# 6_RgbLed.net
KiCad netlist of a schematic drawn in Altium Designer
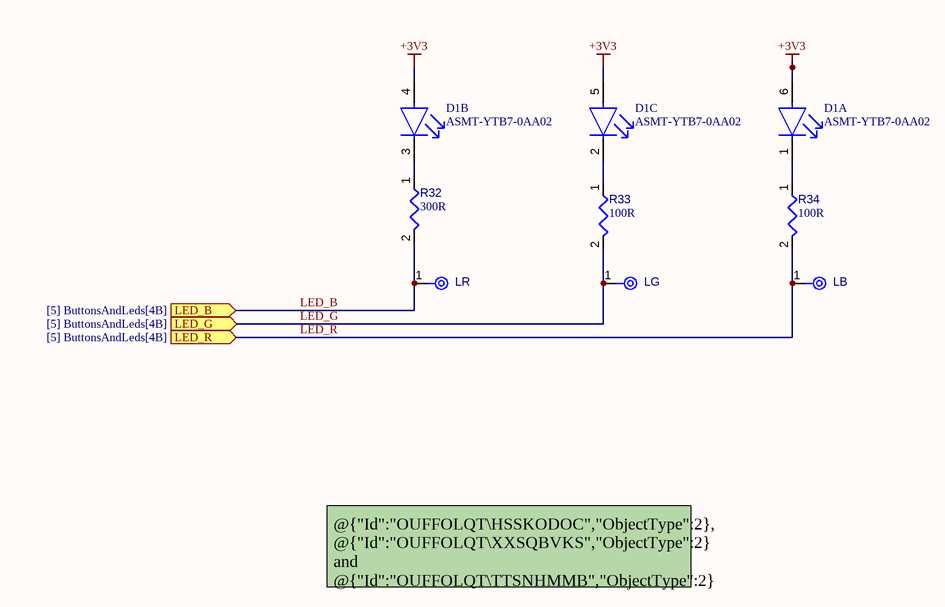
[diagram p0: [6] RgbLed.SchDoc]

(export (version "E")
  (design (tool "Eeschema 10.0.6"))
  (components
    (comp (ref "D1")
      (value "ASMT-YTB7-0AA02")
      (footprint "FP-PLCC-6-MFG")
      (description "LED Tri-Color Blue/Green/Red 469nm/529nm/623nm Chip LED 6-Pin PLCC T/R")
      (libsource (lib "UFCG - Universidade Federal de Campina Grande") (part "0f3d36aaa98356051a15b42400af8f3"))
    )
    (comp (ref "LB")
      (value "TPAD6R")
      (footprint "TP06R")
      (description "0.6mm round")
      (libsource (lib "UFCG - Universidade Federal de Campina Grande") (part "CMP-001-0001-4"))
    )
    (comp (ref "LG")
      (value "TPAD6R")
      (footprint "TP06R")
      (description "0.6mm round")
      (libsource (lib "UFCG - Universidade Federal de Campina Grande") (part "CMP-001-0001-4"))
    )
    (comp (ref "LR")
      (value "TPAD6R")
      (footprint "TP06R")
      (description "0.6mm round")
      (libsource (lib "UFCG - Universidade Federal de Campina Grande") (part "CMP-001-0001-4"))
    )
    (comp (ref "R32")
      (value "300R")
      (footprint "RESC0603(1608)_L")
      (description "Res Thick Film 0603 300 Ohm 5% 1/10W ±200ppm/°C Molded SMD Punched Carrier T/R")
      (fields (field (name "TOLERANCE") "5%") (field (name "Comment") "ERJ-3GEYJ301V"))
      (libsource (lib "UFCG - Universidade Federal de Campina Grande") (part "RES-2"))
    )
    (comp (ref "R33")
      (value "100R")
      (footprint "RESC0603(1608)_L")
      (description "SMD Chip Resistor, 100 Ohm, ï¿½ 1%, 100 mW, 0603 [1608 Metric], Thick Film, Precision")
      (fields (field (name "TOLERANCE") "1%") (field (name "Comment") "ERJ-3EKF1000V"))
      (libsource (lib "UFCG - Universidade Federal de Campina Grande") (part "RES-2"))
    )
    (comp (ref "R34")
      (value "100R")
      (footprint "RESC0603(1608)_L")
      (description "SMD Chip Resistor, 100 Ohm, ï¿½ 1%, 100 mW, 0603 [1608 Metric], Thick Film, Precision")
      (fields (field (name "TOLERANCE") "1%") (field (name "Comment") "ERJ-3EKF1000V"))
      (libsource (lib "UFCG - Universidade Federal de Campina Grande") (part "RES-2"))
    )
  )
  (nets
    (net (code "1") (name "+3V3") (class "Default")
      (node (ref "D1") (pin "4") (pinfunction "Anode(Red)_4") (pintype "passive"))
      (node (ref "D1") (pin "5") (pinfunction "Anode(Green)_5") (pintype "passive"))
      (node (ref "D1") (pin "6") (pinfunction "Anode(Blue)_6") (pintype "passive"))
    )
    (net (code "2") (name "/LED_B") (class "Default")
      (node (ref "LR") (pin "1") (pinfunction "TP_1") (pintype "passive"))
      (node (ref "R32") (pin "2") (pinfunction "2_2") (pintype "passive"))
    )
    (net (code "3") (name "/LED_G") (class "Default")
      (node (ref "LG") (pin "1") (pinfunction "TP_1") (pintype "passive"))
      (node (ref "R33") (pin "2") (pinfunction "2_2") (pintype "passive"))
    )
    (net (code "4") (name "/LED_R") (class "Default")
      (node (ref "LB") (pin "1") (pinfunction "TP_1") (pintype "passive"))
      (node (ref "R34") (pin "2") (pinfunction "2_2") (pintype "passive"))
    )
    (net (code "5") (name "Net-(D1A-Cathode(Blue))") (class "Default")
      (node (ref "D1") (pin "1") (pinfunction "Cathode(Blue)_1") (pintype "passive"))
      (node (ref "R34") (pin "1") (pinfunction "1_1") (pintype "passive"))
    )
    (net (code "6") (name "Net-(D1B-Cathode(Red))") (class "Default")
      (node (ref "D1") (pin "3") (pinfunction "Cathode(Red)_3") (pintype "passive"))
      (node (ref "R32") (pin "1") (pinfunction "1_1") (pintype "passive"))
    )
    (net (code "7") (name "Net-(D1C-Cathode(Green))") (class "Default")
      (node (ref "D1") (pin "2") (pinfunction "Cathode(Green)_2") (pintype "passive"))
      (node (ref "R33") (pin "1") (pinfunction "1_1") (pintype "passive"))
    )
  )
)
